# relay.net
KiCad netlist of a schematic drawn in Altium Designer
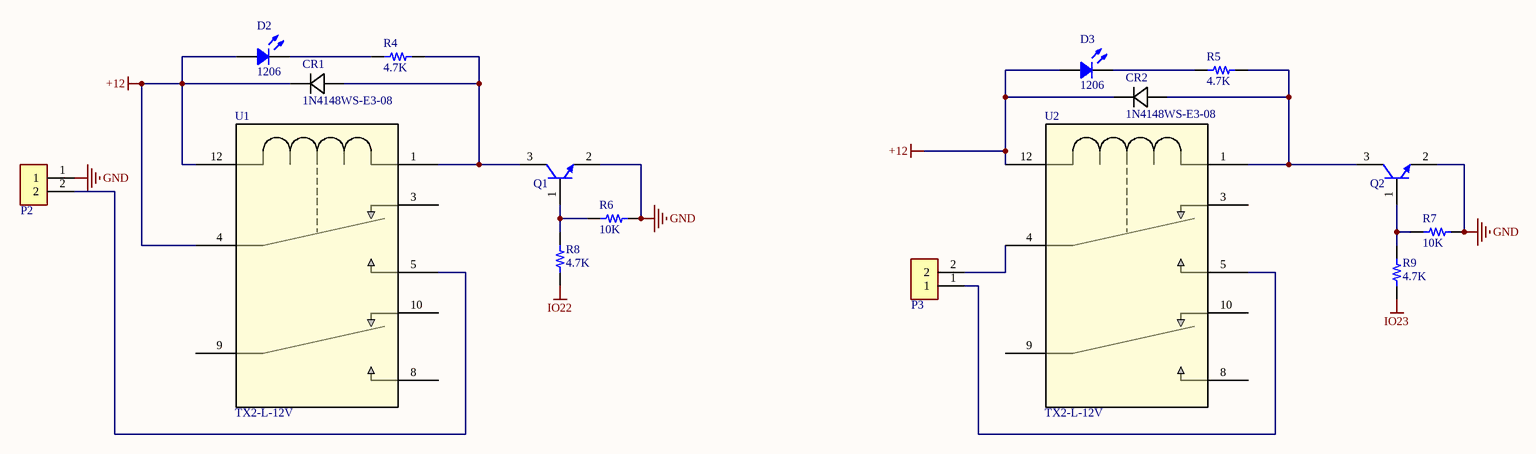
[diagram p0: relay.SchDoc]

(export (version "E")
  (design (tool "Eeschema 10.0.6"))
  (components
    (comp (ref "CR1")
      (value "1N4148WS-E3-08")
      (footprint "CR_WS-E3-08_VIS")
      (description "No Description Available")
      (libsource (lib "1N4148WS-E3-08") (part "1N4148WS-E3-08"))
    )
    (comp (ref "CR2")
      (value "1N4148WS-E3-08")
      (footprint "CR_WS-E3-08_VIS")
      (description "No Description Available")
      (libsource (lib "1N4148WS-E3-08") (part "1N4148WS-E3-08"))
    )
    (comp (ref "D2")
      (value "1206")
      (footprint "LED 1206_3216 YELLOW")
      (description "LED YELLOW CLEAR 2SMD")
      (fields
        (field (name "PART NUMBER") "25-21UYC/S530-A2/TR8")
        (field (name "MANUFACTURER") "Everlight Electronics Co Ltd")
      )
      (libsource (lib "Celestial Altium Library - altium_library") (part "LED"))
    )
    (comp (ref "D3")
      (value "1206")
      (footprint "LED 1206_3216 YELLOW")
      (description "LED YELLOW CLEAR 2SMD")
      (fields
        (field (name "PART NUMBER") "25-21UYC/S530-A2/TR8")
        (field (name "MANUFACTURER") "Everlight Electronics Co Ltd")
      )
      (libsource (lib "Celestial Altium Library - altium_library") (part "LED"))
    )
    (comp (ref "P2")
      (value "282837-2")
      (footprint "TE_282837-2")
      (fields (field (name "MF") "TE Connectivity"))
      (libsource (lib "") (part "282837-2_1"))
    )
    (comp (ref "P3")
      (value "282837-2")
      (footprint "TE_282837-2")
      (fields (field (name "MF") "TE Connectivity"))
      (libsource (lib "connector") (part "282837-2"))
    )
    (comp (ref "Q1")
      (value "BC817-25,215")
      (footprint "NEXPERIA SOT-23-3")
      (description "TRANS NPN 45V 0.5A TO236AB")
      (fields (field (name "MANUFACTURER") "Nexperia USA Inc."))
      (libsource (lib "Celestial Altium Library - altium_library") (part "NEXPERIA NPN SOT-23-3"))
    )
    (comp (ref "Q2")
      (value "BC817-25,215")
      (footprint "NEXPERIA SOT-23-3")
      (description "TRANS NPN 45V 0.5A TO236AB")
      (fields (field (name "MANUFACTURER") "Nexperia USA Inc."))
      (libsource (lib "Celestial Altium Library - altium_library") (part "NEXPERIA NPN SOT-23-3"))
    )
    (comp (ref "R4")
      (value "4.7K")
      (footprint "RES 1206_3216")
      (description "RES SMD 61.9K OHM 1% 1/4W 1206")
      (fields (field (name "PART NUMBER") "CRCW120661K9FKEA") (field (name "MANUFACTURER") "Vishay Dale"))
      (libsource (lib "Celestial Altium Library - altium_library") (part "Resistor"))
    )
    (comp (ref "R5")
      (value "4.7K")
      (footprint "RES 1206_3216")
      (description "RES SMD 61.9K OHM 1% 1/4W 1206")
      (fields (field (name "PART NUMBER") "CRCW120661K9FKEA") (field (name "MANUFACTURER") "Vishay Dale"))
      (libsource (lib "Celestial Altium Library - altium_library") (part "Resistor"))
    )
    (comp (ref "R6")
      (value "10K")
      (footprint "RES 1206_3216")
      (description "RES SMD 61.9K OHM 1% 1/4W 1206")
      (fields (field (name "PART NUMBER") "CRCW120661K9FKEA") (field (name "MANUFACTURER") "Vishay Dale"))
      (libsource (lib "Celestial Altium Library - altium_library") (part "Resistor"))
    )
    (comp (ref "R7")
      (value "10K")
      (footprint "RES 1206_3216")
      (description "RES SMD 61.9K OHM 1% 1/4W 1206")
      (fields (field (name "PART NUMBER") "CRCW120661K9FKEA") (field (name "MANUFACTURER") "Vishay Dale"))
      (libsource (lib "Celestial Altium Library - altium_library") (part "Resistor"))
    )
    (comp (ref "R8")
      (value "4.7K")
      (footprint "RES 1206_3216")
      (description "RES SMD 61.9K OHM 1% 1/4W 1206")
      (fields (field (name "PART NUMBER") "CRCW120661K9FKEA") (field (name "MANUFACTURER") "Vishay Dale"))
      (libsource (lib "Celestial Altium Library - altium_library") (part "Resistor"))
    )
    (comp (ref "R9")
      (value "4.7K")
      (footprint "RES 1206_3216")
      (description "RES SMD 61.9K OHM 1% 1/4W 1206")
      (fields (field (name "PART NUMBER") "CRCW120661K9FKEA") (field (name "MANUFACTURER") "Vishay Dale"))
      (libsource (lib "Celestial Altium Library - altium_library") (part "Resistor"))
    )
    (comp (ref "U1")
      (value "TX2-L-12V")
      (footprint "RELAY_TX2_PAN")
      (description "No Description Available")
      (libsource (lib "TX2-L-12V") (part "TX2-L-12V"))
    )
    (comp (ref "U2")
      (value "TX2-L-12V")
      (footprint "RELAY_TX2_PAN")
      (description "No Description Available")
      (libsource (lib "TX2-L-12V") (part "TX2-L-12V"))
    )
  )
  (nets
    (net (code "1") (name "+12") (class "Default")
      (node (ref "CR1") (pin "1") (pinfunction "1_1") (pintype "passive"))
      (node (ref "CR2") (pin "1") (pinfunction "1_1") (pintype "passive"))
      (node (ref "D2") (pin "1") (pinfunction "1_1") (pintype "passive"))
      (node (ref "D3") (pin "1") (pinfunction "1_1") (pintype "passive"))
      (node (ref "U1") (pin "12") (pinfunction "1_12") (pintype "passive"))
      (node (ref "U1") (pin "4") (pinfunction "3_4") (pintype "passive"))
      (node (ref "U2") (pin "12") (pinfunction "1_12") (pintype "passive"))
    )
    (net (code "2") (name "GND") (class "Default")
      (node (ref "P2") (pin "1") (pinfunction "1_1") (pintype "passive"))
      (node (ref "Q1") (pin "2") (pinfunction "E_2") (pintype "passive"))
      (node (ref "Q2") (pin "2") (pinfunction "E_2") (pintype "passive"))
      (node (ref "R6") (pin "2") (pinfunction "2_2") (pintype "passive"))
      (node (ref "R7") (pin "2") (pinfunction "2_2") (pintype "passive"))
    )
    (net (code "3") (name "IO22") (class "Default")
      (node (ref "R8") (pin "1") (pinfunction "1_1") (pintype "passive"))
    )
    (net (code "4") (name "IO23") (class "Default")
      (node (ref "R9") (pin "1") (pinfunction "1_1") (pintype "passive"))
    )
    (net (code "5") (name "Net-(D2-Pad2)") (class "Default")
      (node (ref "D2") (pin "2") (pinfunction "2_2") (pintype "passive"))
      (node (ref "R4") (pin "2") (pinfunction "2_2") (pintype "passive"))
    )
    (net (code "6") (name "Net-(D3-Pad2)") (class "Default")
      (node (ref "D3") (pin "2") (pinfunction "2_2") (pintype "passive"))
      (node (ref "R5") (pin "2") (pinfunction "2_2") (pintype "passive"))
    )
    (net (code "7") (name "Net-(P3-Pad2)") (class "Default")
      (node (ref "P3") (pin "2") (pinfunction "2_2") (pintype "passive"))
      (node (ref "U2") (pin "4") (pinfunction "3_4") (pintype "passive"))
    )
    (net (code "8") (name "Net-(Q1-B)") (class "Default")
      (node (ref "Q1") (pin "1") (pinfunction "B_1") (pintype "passive"))
      (node (ref "R6") (pin "1") (pinfunction "1_1") (pintype "passive"))
      (node (ref "R8") (pin "2") (pinfunction "2_2") (pintype "passive"))
    )
    (net (code "9") (name "Net-(Q1-C)") (class "Default")
      (node (ref "CR1") (pin "2") (pinfunction "2_2") (pintype "passive"))
      (node (ref "Q1") (pin "3") (pinfunction "C_3") (pintype "passive"))
      (node (ref "R4") (pin "1") (pinfunction "1_1") (pintype "passive"))
      (node (ref "U1") (pin "1") (pinfunction "2_1") (pintype "passive"))
    )
    (net (code "10") (name "Net-(Q2-B)") (class "Default")
      (node (ref "Q2") (pin "1") (pinfunction "B_1") (pintype "passive"))
      (node (ref "R7") (pin "1") (pinfunction "1_1") (pintype "passive"))
      (node (ref "R9") (pin "2") (pinfunction "2_2") (pintype "passive"))
    )
    (net (code "11") (name "Net-(Q2-C)") (class "Default")
      (node (ref "CR2") (pin "2") (pinfunction "2_2") (pintype "passive"))
      (node (ref "Q2") (pin "3") (pinfunction "C_3") (pintype "passive"))
      (node (ref "R5") (pin "1") (pinfunction "1_1") (pintype "passive"))
      (node (ref "U2") (pin "1") (pinfunction "2_1") (pintype "passive"))
    )
    (net (code "12") (name "Net-(U1-4)") (class "Default")
      (node (ref "P2") (pin "2") (pinfunction "2_2") (pintype "passive"))
      (node (ref "U1") (pin "5") (pinfunction "4_5") (pintype "passive"))
    )
    (net (code "13") (name "Net-(U2-4)") (class "Default")
      (node (ref "P3") (pin "1") (pinfunction "1_1") (pintype "passive"))
      (node (ref "U2") (pin "5") (pinfunction "4_5") (pintype "passive"))
    )
    (net (code "14") (name "unconnected-(U1-3-Pad8)") (class "Default")
      (node (ref "U1") (pin "8") (pinfunction "3_8") (pintype "passive"))
    )
    (net (code "15") (name "unconnected-(U1-5-Pad3)") (class "Default")
      (node (ref "U1") (pin "3") (pinfunction "5_3") (pintype "passive"))
    )
    (net (code "16") (name "unconnected-(U1-6-Pad9)") (class "Default")
      (node (ref "U1") (pin "9") (pinfunction "6_9") (pintype "passive"))
    )
    (net (code "17") (name "unconnected-(U1-8-Pad10)") (class "Default")
      (node (ref "U1") (pin "10") (pinfunction "8_10") (pintype "passive"))
    )
    (net (code "18") (name "unconnected-(U2-3-Pad8)") (class "Default")
      (node (ref "U2") (pin "8") (pinfunction "3_8") (pintype "passive"))
    )
    (net (code "19") (name "unconnected-(U2-5-Pad3)") (class "Default")
      (node (ref "U2") (pin "3") (pinfunction "5_3") (pintype "passive"))
    )
    (net (code "20") (name "unconnected-(U2-6-Pad9)") (class "Default")
      (node (ref "U2") (pin "9") (pinfunction "6_9") (pintype "passive"))
    )
    (net (code "21") (name "unconnected-(U2-8-Pad10)") (class "Default")
      (node (ref "U2") (pin "10") (pinfunction "8_10") (pintype "passive"))
    )
  )
)
